# design.net
KiCad netlist of a schematic drawn in EasyEDA Pro
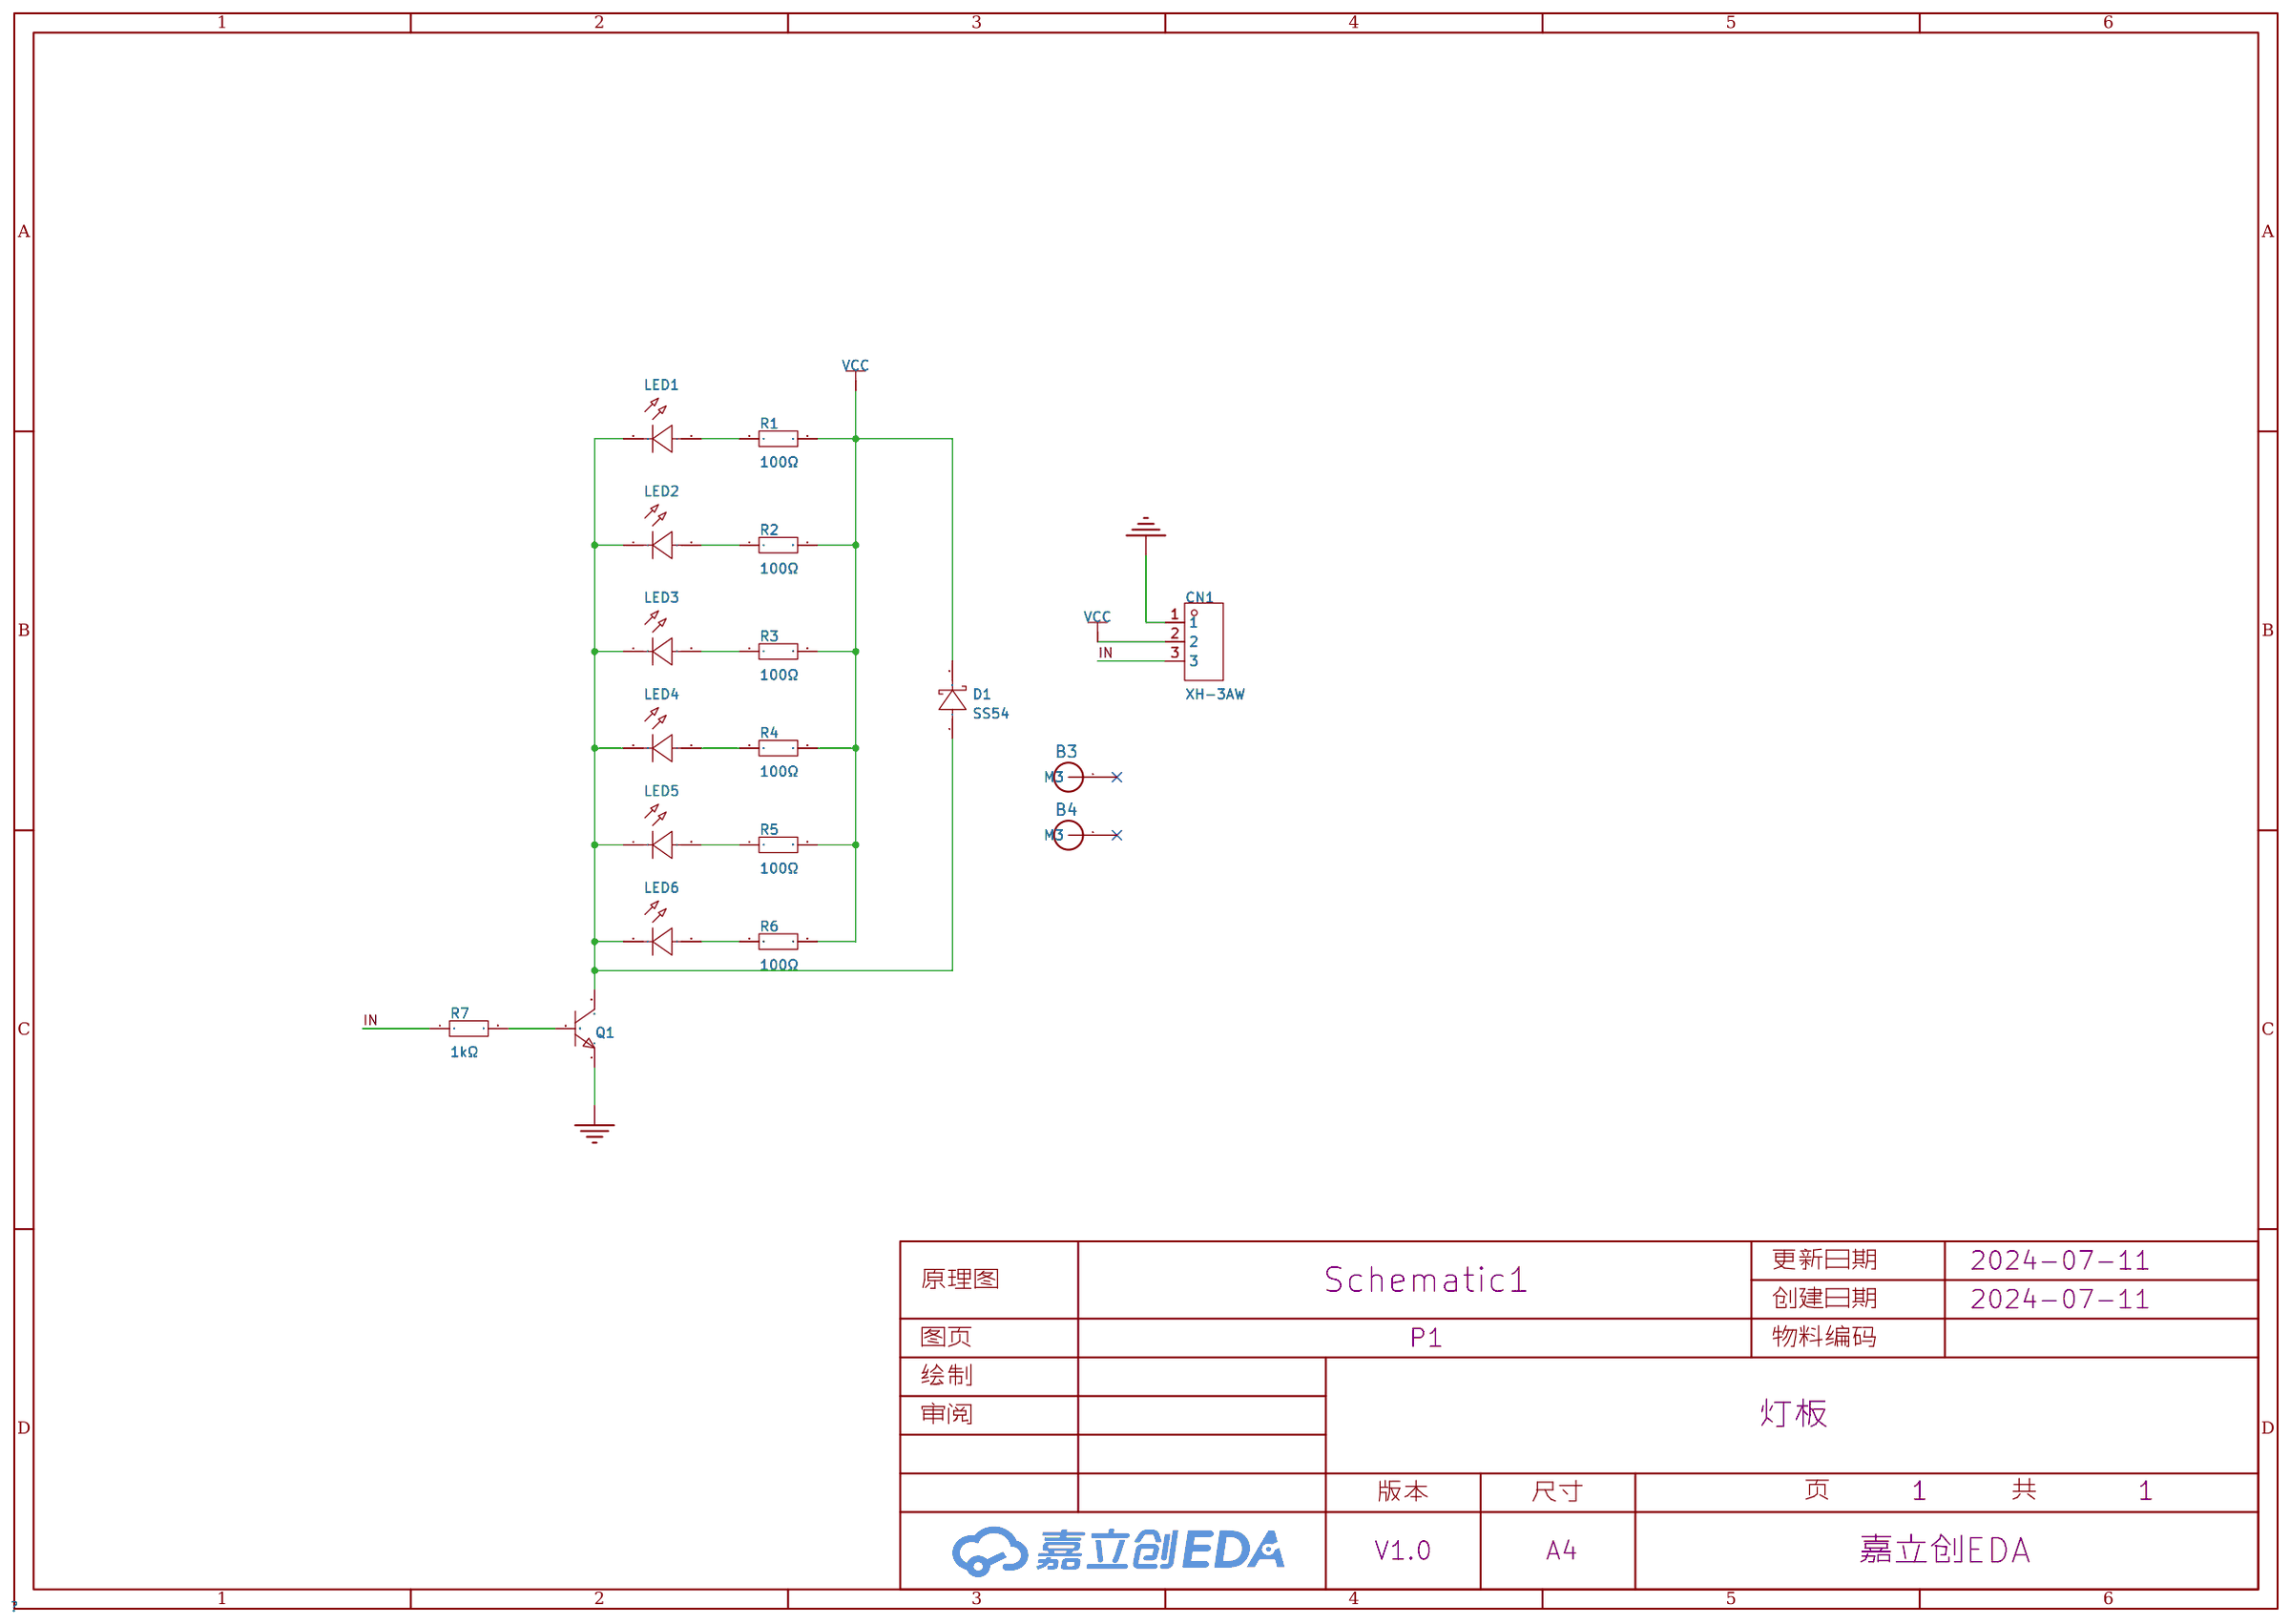
[diagram p0: schematic sheet]

(export (version "E")
  (design (tool "Eeschema 10.0.6"))
  (components
    (comp (ref "B3")
      (value "M3螺柱孔_JX")
      (footprint "easyedapro:M3")
      (libsource (lib "easyedapro") (part "M3螺柱孔_JX"))
    )
    (comp (ref "B4")
      (value "M3螺柱孔_JX")
      (footprint "easyedapro:M3")
      (libsource (lib "easyedapro") (part "M3螺柱孔_JX"))
    )
    (comp (ref "CN1")
      (value "XH-3AW")
      (footprint "easyedapro:CONN-TH_3P-P2.54_HCTL_XH-3AW")
      (fields (field (name "Manufacturer") "HCTL(华灿天禄)"))
      (libsource (lib "easyedapro") (part "XH-3AW_C2908612"))
    )
    (comp (ref "D1")
      (value "SS54")
      (footprint "easyedapro:SMA_L4.3-W2.6-LS5.0-FD")
      (description "二极管配置:独立式;正向压降(Vf):550mV@5.0A;直流反向耐压(Vr):40V;平均整流电流(Io):5A;")
      (fields (field (name "Manufacturer") "宏迦橙"))
      (libsource (lib "easyedapro") (part "SS54_C7420369"))
    )
    (comp (ref "LED1")
      (value "HL-A-3528H343W-S1-13HL-HR3(SDCM")
      (footprint "easyedapro:LED-SMD_L3.2-W2.8-LS3.5-RD_WHITE")
      (fields (field (name "Manufacturer") "HONGLITRONIC(鸿利光电)"))
      (libsource (lib "easyedapro") (part "HL-A-3528H343W-S1-13HL-HR3(SDCM{lt}6)(4750K-5300K)"))
    )
    (comp (ref "LED2")
      (value "HL-A-3528H343W-S1-13HL-HR3(SDCM")
      (footprint "easyedapro:LED-SMD_L3.2-W2.8-LS3.5-RD_WHITE")
      (fields (field (name "Manufacturer") "HONGLITRONIC(鸿利光电)"))
      (libsource (lib "easyedapro") (part "HL-A-3528H343W-S1-13HL-HR3(SDCM{lt}6)(4750K-5300K)"))
    )
    (comp (ref "LED3")
      (value "HL-A-3528H343W-S1-13HL-HR3(SDCM")
      (footprint "easyedapro:LED-SMD_L3.2-W2.8-LS3.5-RD_WHITE")
      (fields (field (name "Manufacturer") "HONGLITRONIC(鸿利光电)"))
      (libsource (lib "easyedapro") (part "HL-A-3528H343W-S1-13HL-HR3(SDCM{lt}6)(4750K-5300K)"))
    )
    (comp (ref "LED4")
      (value "HL-A-3528H343W-S1-13HL-HR3(SDCM")
      (footprint "easyedapro:LED-SMD_L3.2-W2.8-LS3.5-RD_WHITE")
      (fields (field (name "Manufacturer") "HONGLITRONIC(鸿利光电)"))
      (libsource (lib "easyedapro") (part "HL-A-3528H343W-S1-13HL-HR3(SDCM{lt}6)(4750K-5300K)"))
    )
    (comp (ref "LED5")
      (value "HL-A-3528H343W-S1-13HL-HR3(SDCM")
      (footprint "easyedapro:LED-SMD_L3.2-W2.8-LS3.5-RD_WHITE")
      (fields (field (name "Manufacturer") "HONGLITRONIC(鸿利光电)"))
      (libsource (lib "easyedapro") (part "HL-A-3528H343W-S1-13HL-HR3(SDCM{lt}6)(4750K-5300K)"))
    )
    (comp (ref "LED6")
      (value "HL-A-3528H343W-S1-13HL-HR3(SDCM")
      (footprint "easyedapro:LED-SMD_L3.2-W2.8-LS3.5-RD_WHITE")
      (fields (field (name "Manufacturer") "HONGLITRONIC(鸿利光电)"))
      (libsource (lib "easyedapro") (part "HL-A-3528H343W-S1-13HL-HR3(SDCM{lt}6)(4750K-5300K)"))
    )
    (comp (ref "Q1")
      (value "PBSS4350X,115")
      (footprint "easyedapro:SOT-89-3_L4.5-W2.5-P1.50-LS4.0-TR")
      (description "晶体管类型:NPN;集电极电流(Ic):3A;集射极击穿电压(Vceo):50V;功率(Pd):1.6W;直流电流增益(hFE@Ic,Vce):300@1A,2V;")
      (fields (field (name "Manufacturer") "Nexperia(安世)"))
      (libsource (lib "easyedapro") (part "PBSS4350X,115"))
    )
    (comp (ref "R1")
      (value "100Ω")
      (footprint "easyedapro:R0603")
      (description "电阻类型:厚膜电阻;阻值:100Ω;精度:±1%;功率:100mW;最大工作电压:75V;温度系数:±100ppm/°C;")
      (fields (field (name "Manufacturer Part") "RC0603FR-07100RL") (field (name "Manufacturer") "YAGEO(国巨)"))
      (libsource (lib "easyedapro") (part "RC0603FR-07100RL"))
    )
    (comp (ref "R2")
      (value "100Ω")
      (footprint "easyedapro:R0603")
      (description "电阻类型:厚膜电阻;阻值:100Ω;精度:±1%;功率:100mW;最大工作电压:75V;温度系数:±100ppm/°C;")
      (fields (field (name "Manufacturer Part") "RC0603FR-07100RL") (field (name "Manufacturer") "YAGEO(国巨)"))
      (libsource (lib "easyedapro") (part "RC0603FR-07100RL"))
    )
    (comp (ref "R3")
      (value "100Ω")
      (footprint "easyedapro:R0603")
      (description "电阻类型:厚膜电阻;阻值:100Ω;精度:±1%;功率:100mW;最大工作电压:75V;温度系数:±100ppm/°C;")
      (fields (field (name "Manufacturer Part") "RC0603FR-07100RL") (field (name "Manufacturer") "YAGEO(国巨)"))
      (libsource (lib "easyedapro") (part "RC0603FR-07100RL"))
    )
    (comp (ref "R4")
      (value "100Ω")
      (footprint "easyedapro:R0603")
      (description "电阻类型:厚膜电阻;阻值:100Ω;精度:±1%;功率:100mW;最大工作电压:75V;温度系数:±100ppm/°C;")
      (fields (field (name "Manufacturer Part") "RC0603FR-07100RL") (field (name "Manufacturer") "YAGEO(国巨)"))
      (libsource (lib "easyedapro") (part "RC0603FR-07100RL"))
    )
    (comp (ref "R5")
      (value "100Ω")
      (footprint "easyedapro:R0603")
      (description "电阻类型:厚膜电阻;阻值:100Ω;精度:±1%;功率:100mW;最大工作电压:75V;温度系数:±100ppm/°C;")
      (fields (field (name "Manufacturer Part") "RC0603FR-07100RL") (field (name "Manufacturer") "YAGEO(国巨)"))
      (libsource (lib "easyedapro") (part "RC0603FR-07100RL"))
    )
    (comp (ref "R6")
      (value "100Ω")
      (footprint "easyedapro:R0603")
      (description "电阻类型:厚膜电阻;阻值:100Ω;精度:±1%;功率:100mW;最大工作电压:75V;温度系数:±100ppm/°C;")
      (fields (field (name "Manufacturer Part") "RC0603FR-07100RL") (field (name "Manufacturer") "YAGEO(国巨)"))
      (libsource (lib "easyedapro") (part "RC0603FR-07100RL"))
    )
    (comp (ref "R7")
      (value "1kΩ")
      (footprint "easyedapro:R0603")
      (description "电阻类型:厚膜电阻;阻值:1kΩ;精度:±1%;功率:100mW;")
      (fields
        (field (name "Manufacturer Part") "0603WAF1001T5E")
        (field (name "Manufacturer") "UNI-ROYAL(厚声)")
      )
      (libsource (lib "easyedapro") (part "0603WAF1001T5E"))
    )
  )
  (nets
    (net (code "1") (name "/IN") (class "Default")
      (node (ref "CN1") (pin "3") (pinfunction "3_3") (pintype "unspecified"))
      (node (ref "R7") (pin "1") (pinfunction "1_1") (pintype "input"))
    )
    (net (code "2") (name "GND") (class "Default")
      (node (ref "CN1") (pin "1") (pinfunction "1_1") (pintype "unspecified"))
      (node (ref "Q1") (pin "1") (pinfunction "E_1") (pintype "unspecified"))
    )
    (net (code "3") (name "Net-(D1-A)") (class "Default")
      (node (ref "D1") (pin "1") (pinfunction "A_1") (pintype "unspecified"))
      (node (ref "LED1") (pin "1") (pinfunction "K_1") (pintype "unspecified"))
      (node (ref "LED2") (pin "1") (pinfunction "K_1") (pintype "unspecified"))
      (node (ref "LED3") (pin "1") (pinfunction "K_1") (pintype "unspecified"))
      (node (ref "LED4") (pin "1") (pinfunction "K_1") (pintype "unspecified"))
      (node (ref "LED5") (pin "1") (pinfunction "K_1") (pintype "unspecified"))
      (node (ref "LED6") (pin "1") (pinfunction "K_1") (pintype "unspecified"))
      (node (ref "Q1") (pin "2") (pinfunction "C_2") (pintype "unspecified"))
    )
    (net (code "4") (name "Net-(LED1-A)") (class "Default")
      (node (ref "LED1") (pin "2") (pinfunction "A_2") (pintype "unspecified"))
      (node (ref "R1") (pin "1") (pinfunction "1_1") (pintype "input"))
    )
    (net (code "5") (name "Net-(LED2-A)") (class "Default")
      (node (ref "LED2") (pin "2") (pinfunction "A_2") (pintype "unspecified"))
      (node (ref "R2") (pin "1") (pinfunction "1_1") (pintype "input"))
    )
    (net (code "6") (name "Net-(LED3-A)") (class "Default")
      (node (ref "LED3") (pin "2") (pinfunction "A_2") (pintype "unspecified"))
      (node (ref "R3") (pin "1") (pinfunction "1_1") (pintype "input"))
    )
    (net (code "7") (name "Net-(LED4-A)") (class "Default")
      (node (ref "LED4") (pin "2") (pinfunction "A_2") (pintype "unspecified"))
      (node (ref "R4") (pin "1") (pinfunction "1_1") (pintype "input"))
    )
    (net (code "8") (name "Net-(LED5-A)") (class "Default")
      (node (ref "LED5") (pin "2") (pinfunction "A_2") (pintype "unspecified"))
      (node (ref "R5") (pin "1") (pinfunction "1_1") (pintype "input"))
    )
    (net (code "9") (name "Net-(LED6-A)") (class "Default")
      (node (ref "LED6") (pin "2") (pinfunction "A_2") (pintype "unspecified"))
      (node (ref "R6") (pin "1") (pinfunction "1_1") (pintype "input"))
    )
    (net (code "10") (name "Net-(Q1-B)") (class "Default")
      (node (ref "Q1") (pin "3") (pinfunction "B_3") (pintype "unspecified"))
      (node (ref "R7") (pin "2") (pinfunction "2_2") (pintype "input"))
    )
    (net (code "11") (name "VCC") (class "Default")
      (node (ref "CN1") (pin "2") (pinfunction "2_2") (pintype "unspecified"))
      (node (ref "D1") (pin "2") (pinfunction "K_2") (pintype "unspecified"))
      (node (ref "R1") (pin "2") (pinfunction "2_2") (pintype "input"))
      (node (ref "R2") (pin "2") (pinfunction "2_2") (pintype "input"))
      (node (ref "R3") (pin "2") (pinfunction "2_2") (pintype "input"))
      (node (ref "R4") (pin "2") (pinfunction "2_2") (pintype "input"))
      (node (ref "R5") (pin "2") (pinfunction "2_2") (pintype "input"))
      (node (ref "R6") (pin "2") (pinfunction "2_2") (pintype "input"))
    )
    (net (code "12") (name "unconnected-(B3-M3-Pad1)") (class "Default")
      (node (ref "B3") (pin "1") (pinfunction "M3_1") (pintype "input+no_connect"))
    )
    (net (code "13") (name "unconnected-(B4-M3-Pad1)") (class "Default")
      (node (ref "B4") (pin "1") (pinfunction "M3_1") (pintype "input+no_connect"))
    )
  )
)
